# spartan6-2.net
KiCad netlist of a schematic drawn in Altium Designer
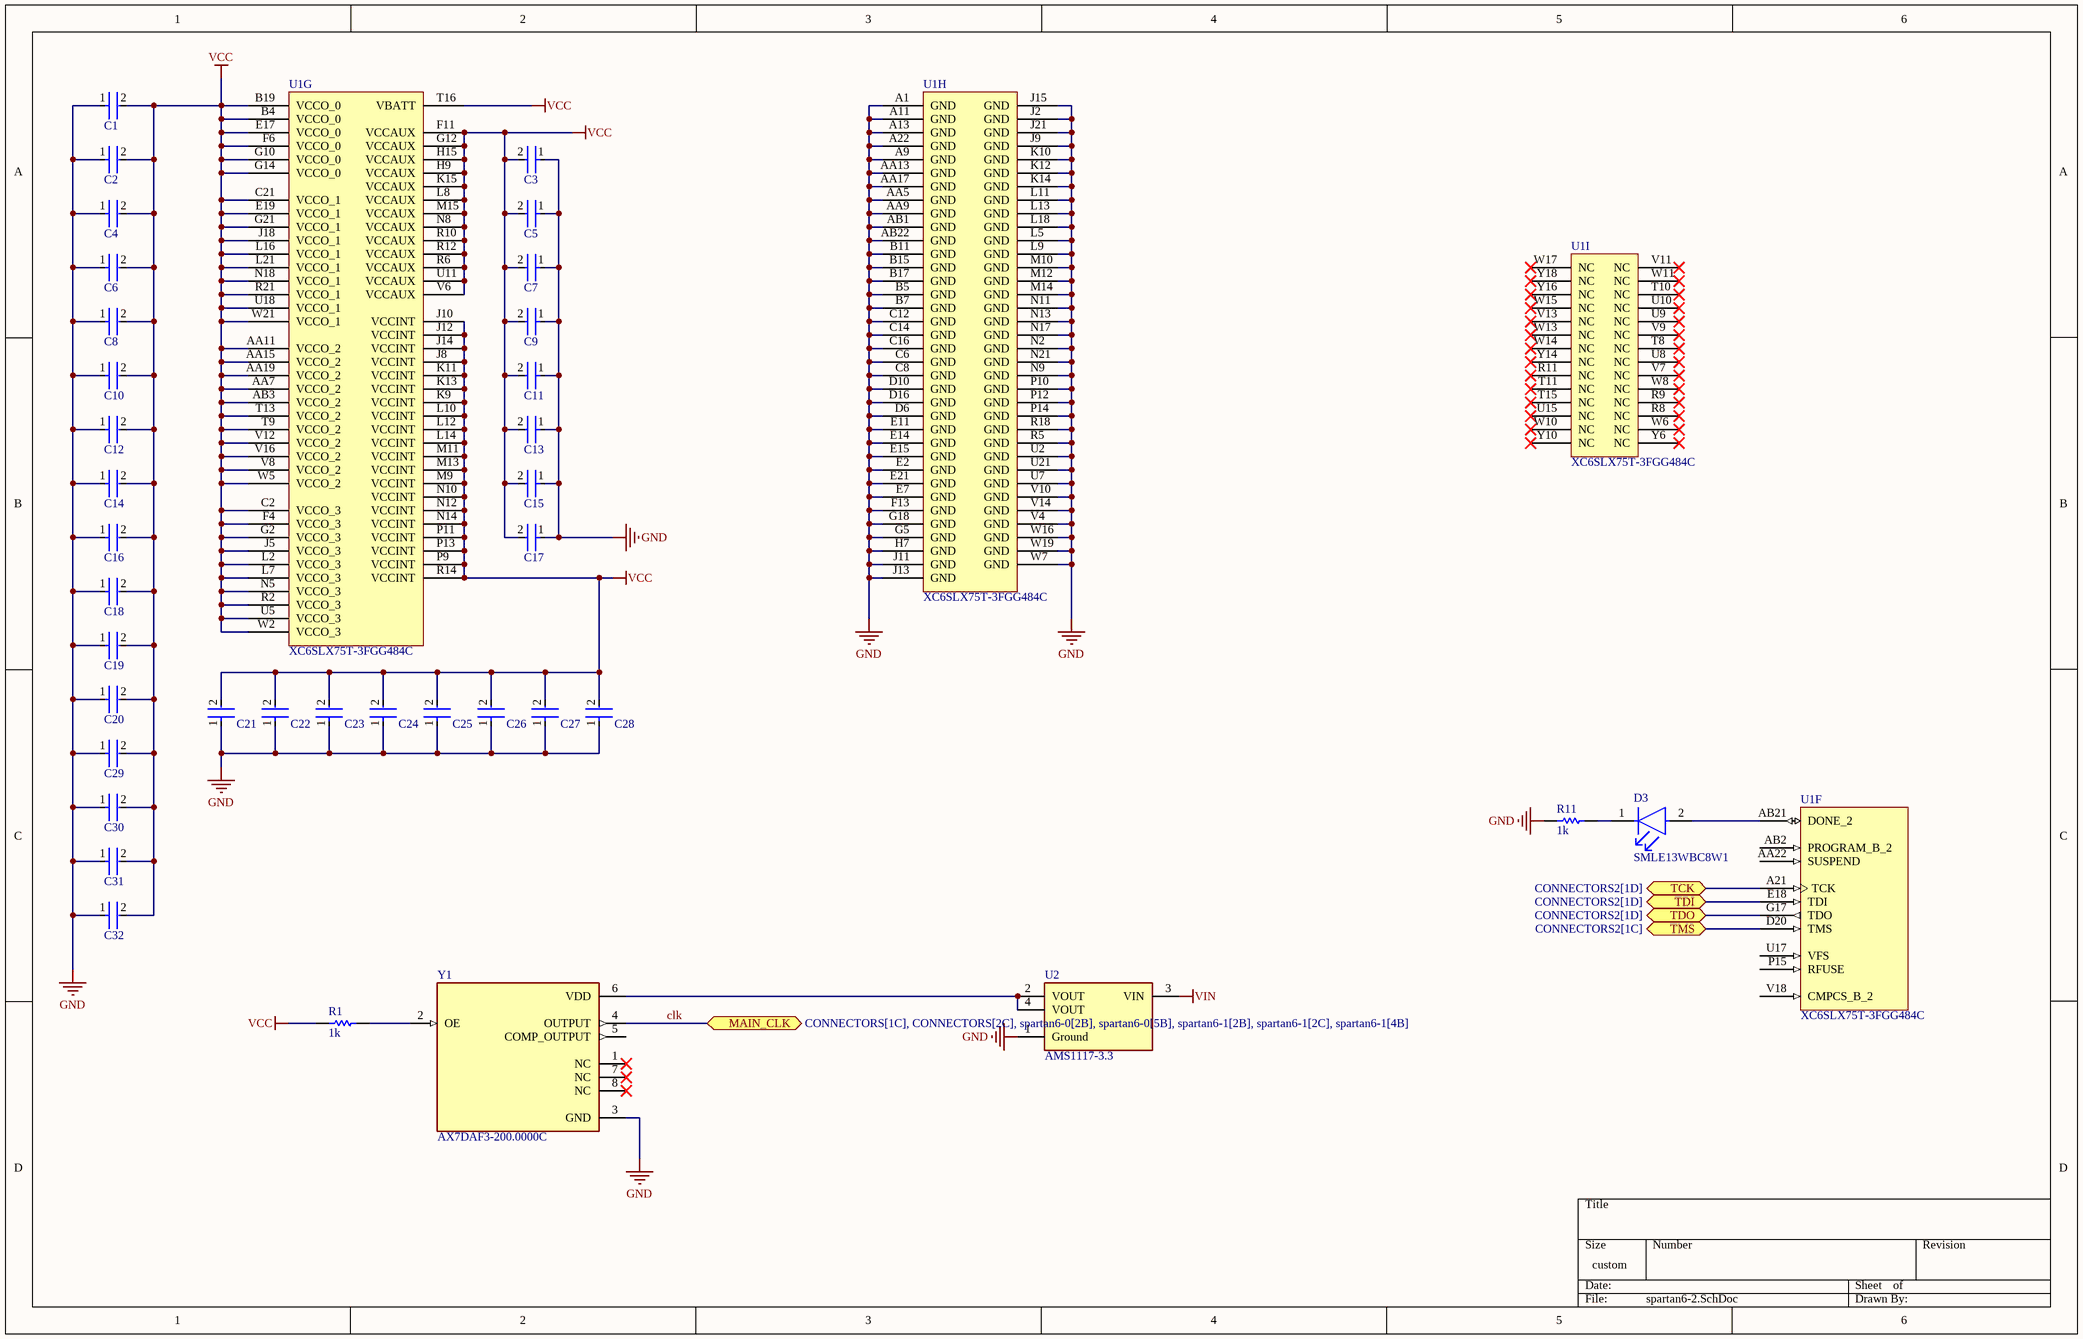
[diagram p0: spartan6-2.SchDoc]

(export (version "E")
  (design (tool "Eeschema 10.0.6"))
  (components
    (comp (ref "C1")
      (value "C0603X6S0G474M030BC")
      (footprint "FP-C0603-030-0_03-MFG")
      (description "Multilayer Ceramic Capacitors 470nF ±20% 4V X6S SMD 0201")
      (fields (field (name "TOLERANCE") "20%"))
      (libsource (lib "Altium Content Vault") (part "02cd4be3c70576c341d710602a673aa"))
    )
    (comp (ref "C2")
      (value "C0603X6S0G474M030BC")
      (footprint "FP-C0603-030-0_03-MFG")
      (description "Multilayer Ceramic Capacitors 470nF ±20% 4V X6S SMD 0201")
      (fields (field (name "TOLERANCE") "20%"))
      (libsource (lib "Altium Content Vault") (part "02cd4be3c70576c341d710602a673aa"))
    )
    (comp (ref "C3")
      (value "C0603X6S0G474M030BC")
      (footprint "FP-C0603-030-0_03-MFG")
      (description "Multilayer Ceramic Capacitors 470nF ±20% 4V X6S SMD 0201")
      (fields (field (name "TOLERANCE") "20%"))
      (libsource (lib "Altium Content Vault") (part "02cd4be3c70576c341d710602a673aa"))
    )
    (comp (ref "C4")
      (value "C0603X6S0G474M030BC")
      (footprint "FP-C0603-030-0_03-MFG")
      (description "Multilayer Ceramic Capacitors 470nF ±20% 4V X6S SMD 0201")
      (fields (field (name "TOLERANCE") "20%"))
      (libsource (lib "Altium Content Vault") (part "02cd4be3c70576c341d710602a673aa"))
    )
    (comp (ref "C5")
      (value "C0603X6S0G474M030BC")
      (footprint "FP-C0603-030-0_03-MFG")
      (description "Multilayer Ceramic Capacitors 470nF ±20% 4V X6S SMD 0201")
      (fields (field (name "TOLERANCE") "20%"))
      (libsource (lib "Altium Content Vault") (part "02cd4be3c70576c341d710602a673aa"))
    )
    (comp (ref "C6")
      (value "C0603X6S0G474M030BC")
      (footprint "FP-C0603-030-0_03-MFG")
      (description "Multilayer Ceramic Capacitors 470nF ±20% 4V X6S SMD 0201")
      (fields (field (name "TOLERANCE") "20%"))
      (libsource (lib "Altium Content Vault") (part "02cd4be3c70576c341d710602a673aa"))
    )
    (comp (ref "C7")
      (value "C0603X6S0G474M030BC")
      (footprint "FP-C0603-030-0_03-MFG")
      (description "Multilayer Ceramic Capacitors 470nF ±20% 4V X6S SMD 0201")
      (fields (field (name "TOLERANCE") "20%"))
      (libsource (lib "Altium Content Vault") (part "02cd4be3c70576c341d710602a673aa"))
    )
    (comp (ref "C8")
      (value "C0603X6S0G474M030BC")
      (footprint "FP-C0603-030-0_03-MFG")
      (description "Multilayer Ceramic Capacitors 470nF ±20% 4V X6S SMD 0201")
      (fields (field (name "TOLERANCE") "20%"))
      (libsource (lib "Altium Content Vault") (part "02cd4be3c70576c341d710602a673aa"))
    )
    (comp (ref "C9")
      (value "C0603X6S0G474M030BC")
      (footprint "FP-C0603-030-0_03-MFG")
      (description "Multilayer Ceramic Capacitors 470nF ±20% 4V X6S SMD 0201")
      (fields (field (name "TOLERANCE") "20%"))
      (libsource (lib "Altium Content Vault") (part "02cd4be3c70576c341d710602a673aa"))
    )
    (comp (ref "C10")
      (value "C0603X6S0G474M030BC")
      (footprint "FP-C0603-030-0_03-MFG")
      (description "Multilayer Ceramic Capacitors 470nF ±20% 4V X6S SMD 0201")
      (fields (field (name "TOLERANCE") "20%"))
      (libsource (lib "Altium Content Vault") (part "02cd4be3c70576c341d710602a673aa"))
    )
    (comp (ref "C11")
      (value "C0603X6S0G474M030BC")
      (footprint "FP-C0603-030-0_03-MFG")
      (description "Multilayer Ceramic Capacitors 470nF ±20% 4V X6S SMD 0201")
      (fields (field (name "TOLERANCE") "20%"))
      (libsource (lib "Altium Content Vault") (part "02cd4be3c70576c341d710602a673aa"))
    )
    (comp (ref "C12")
      (value "C0603X6S0G474M030BC")
      (footprint "FP-C0603-030-0_03-MFG")
      (description "Multilayer Ceramic Capacitors 470nF ±20% 4V X6S SMD 0201")
      (fields (field (name "TOLERANCE") "20%"))
      (libsource (lib "Altium Content Vault") (part "02cd4be3c70576c341d710602a673aa"))
    )
    (comp (ref "C13")
      (value "C0603X6S0G474M030BC")
      (footprint "FP-C0603-030-0_03-MFG")
      (description "Multilayer Ceramic Capacitors 470nF ±20% 4V X6S SMD 0201")
      (fields (field (name "TOLERANCE") "20%"))
      (libsource (lib "Altium Content Vault") (part "02cd4be3c70576c341d710602a673aa"))
    )
    (comp (ref "C14")
      (value "C0603X6S0G474M030BC")
      (footprint "FP-C0603-030-0_03-MFG")
      (description "Multilayer Ceramic Capacitors 470nF ±20% 4V X6S SMD 0201")
      (fields (field (name "TOLERANCE") "20%"))
      (libsource (lib "Altium Content Vault") (part "02cd4be3c70576c341d710602a673aa"))
    )
    (comp (ref "C15")
      (value "C0603X6S0G474M030BC")
      (footprint "FP-C0603-030-0_03-MFG")
      (description "Multilayer Ceramic Capacitors 470nF ±20% 4V X6S SMD 0201")
      (fields (field (name "TOLERANCE") "20%"))
      (libsource (lib "Altium Content Vault") (part "02cd4be3c70576c341d710602a673aa"))
    )
    (comp (ref "C16")
      (value "C0603X6S0G474M030BC")
      (footprint "FP-C0603-030-0_03-MFG")
      (description "Multilayer Ceramic Capacitors 470nF ±20% 4V X6S SMD 0201")
      (fields (field (name "TOLERANCE") "20%"))
      (libsource (lib "Altium Content Vault") (part "02cd4be3c70576c341d710602a673aa"))
    )
    (comp (ref "C17")
      (value "C0603X6S0G474M030BC")
      (footprint "FP-C0603-030-0_03-MFG")
      (description "Multilayer Ceramic Capacitors 470nF ±20% 4V X6S SMD 0201")
      (fields (field (name "TOLERANCE") "20%"))
      (libsource (lib "Altium Content Vault") (part "02cd4be3c70576c341d710602a673aa"))
    )
    (comp (ref "C18")
      (value "C0603X6S0G474M030BC")
      (footprint "FP-C0603-030-0_03-MFG")
      (description "Multilayer Ceramic Capacitors 470nF ±20% 4V X6S SMD 0201")
      (fields (field (name "TOLERANCE") "20%"))
      (libsource (lib "Altium Content Vault") (part "02cd4be3c70576c341d710602a673aa"))
    )
    (comp (ref "C19")
      (value "C0603X6S0G474M030BC")
      (footprint "FP-C0603-030-0_03-MFG")
      (description "Multilayer Ceramic Capacitors 470nF ±20% 4V X6S SMD 0201")
      (fields (field (name "TOLERANCE") "20%"))
      (libsource (lib "Altium Content Vault") (part "02cd4be3c70576c341d710602a673aa"))
    )
    (comp (ref "C20")
      (value "C0603X6S0G474M030BC")
      (footprint "FP-C0603-030-0_03-MFG")
      (description "Multilayer Ceramic Capacitors 470nF ±20% 4V X6S SMD 0201")
      (fields (field (name "TOLERANCE") "20%"))
      (libsource (lib "Altium Content Vault") (part "02cd4be3c70576c341d710602a673aa"))
    )
    (comp (ref "C21")
      (value "C0603X6S0G474M030BC")
      (footprint "FP-C0603-030-0_03-MFG")
      (description "Multilayer Ceramic Capacitors 470nF ±20% 4V X6S SMD 0201")
      (fields (field (name "TOLERANCE") "20%"))
      (libsource (lib "Altium Content Vault") (part "02cd4be3c70576c341d710602a673aa"))
    )
    (comp (ref "C22")
      (value "C0603X6S0G474M030BC")
      (footprint "FP-C0603-030-0_03-MFG")
      (description "Multilayer Ceramic Capacitors 470nF ±20% 4V X6S SMD 0201")
      (fields (field (name "TOLERANCE") "20%"))
      (libsource (lib "Altium Content Vault") (part "02cd4be3c70576c341d710602a673aa"))
    )
    (comp (ref "C23")
      (value "C0603X6S0G474M030BC")
      (footprint "FP-C0603-030-0_03-MFG")
      (description "Multilayer Ceramic Capacitors 470nF ±20% 4V X6S SMD 0201")
      (fields (field (name "TOLERANCE") "20%"))
      (libsource (lib "Altium Content Vault") (part "02cd4be3c70576c341d710602a673aa"))
    )
    (comp (ref "C24")
      (value "C0603X6S0G474M030BC")
      (footprint "FP-C0603-030-0_03-MFG")
      (description "Multilayer Ceramic Capacitors 470nF ±20% 4V X6S SMD 0201")
      (fields (field (name "TOLERANCE") "20%"))
      (libsource (lib "Altium Content Vault") (part "02cd4be3c70576c341d710602a673aa"))
    )
    (comp (ref "C25")
      (value "C0603X6S0G474M030BC")
      (footprint "FP-C0603-030-0_03-MFG")
      (description "Multilayer Ceramic Capacitors 470nF ±20% 4V X6S SMD 0201")
      (fields (field (name "TOLERANCE") "20%"))
      (libsource (lib "Altium Content Vault") (part "02cd4be3c70576c341d710602a673aa"))
    )
    (comp (ref "C26")
      (value "C0603X6S0G474M030BC")
      (footprint "FP-C0603-030-0_03-MFG")
      (description "Multilayer Ceramic Capacitors 470nF ±20% 4V X6S SMD 0201")
      (fields (field (name "TOLERANCE") "20%"))
      (libsource (lib "Altium Content Vault") (part "02cd4be3c70576c341d710602a673aa"))
    )
    (comp (ref "C27")
      (value "C0603X6S0G474M030BC")
      (footprint "FP-C0603-030-0_03-MFG")
      (description "Multilayer Ceramic Capacitors 470nF ±20% 4V X6S SMD 0201")
      (fields (field (name "TOLERANCE") "20%"))
      (libsource (lib "Altium Content Vault") (part "02cd4be3c70576c341d710602a673aa"))
    )
    (comp (ref "C28")
      (value "C0603X6S0G474M030BC")
      (footprint "FP-C0603-030-0_03-MFG")
      (description "Multilayer Ceramic Capacitors 470nF ±20% 4V X6S SMD 0201")
      (fields (field (name "TOLERANCE") "20%"))
      (libsource (lib "Altium Content Vault") (part "02cd4be3c70576c341d710602a673aa"))
    )
    (comp (ref "C29")
      (value "C0603X6S0G474M030BC")
      (footprint "FP-C0603-030-0_03-MFG")
      (description "Multilayer Ceramic Capacitors 470nF ±20% 4V X6S SMD 0201")
      (fields (field (name "TOLERANCE") "20%"))
      (libsource (lib "Altium Content Vault") (part "02cd4be3c70576c341d710602a673aa"))
    )
    (comp (ref "C30")
      (value "C0603X6S0G474M030BC")
      (footprint "FP-C0603-030-0_03-MFG")
      (description "Multilayer Ceramic Capacitors 470nF ±20% 4V X6S SMD 0201")
      (fields (field (name "TOLERANCE") "20%"))
      (libsource (lib "Altium Content Vault") (part "02cd4be3c70576c341d710602a673aa"))
    )
    (comp (ref "C31")
      (value "C0603X6S0G474M030BC")
      (footprint "FP-C0603-030-0_03-MFG")
      (description "Multilayer Ceramic Capacitors 470nF ±20% 4V X6S SMD 0201")
      (fields (field (name "TOLERANCE") "20%"))
      (libsource (lib "Altium Content Vault") (part "02cd4be3c70576c341d710602a673aa"))
    )
    (comp (ref "C32")
      (value "C0603X6S0G474M030BC")
      (footprint "FP-C0603-030-0_03-MFG")
      (description "Multilayer Ceramic Capacitors 470nF ±20% 4V X6S SMD 0201")
      (fields (field (name "TOLERANCE") "20%"))
      (libsource (lib "Altium Content Vault") (part "02cd4be3c70576c341d710602a673aa"))
    )
    (comp (ref "D3")
      (value "SMLE13WBC8W1")
      (footprint "FP-SMLE13WBC8W1-MFG")
      (description "LED WHITE 0603 SMD")
      (fields
        (field (name "OCTOPART") "https://octopart.com/smle13wbc8w1-rohm-22224565")
        (field (name "MANUFACTURER") "Rohm")
      )
      (libsource (lib "Altium Content Vault") (part "8706943c75ba83719d021d2fdc84c58"))
    )
    (comp (ref "R1")
      (value "1k")
      (footprint "RESC2013X60X35ML10T20")
      (fields (field (name "TOLERANCE") "5%") (field (name "MANUFACTURER") "Yageo"))
      (libsource (lib "Altium Content Vault") (part "RES-2"))
    )
    (comp (ref "R11")
      (value "1k")
      (footprint "RESC2013X60X35ML10T20")
      (fields (field (name "TOLERANCE") "5%") (field (name "MANUFACTURER") "Yageo"))
      (libsource (lib "Altium Content Vault") (part "RES-2"))
    )
    (comp (ref "U1")
      (value "XC6SLX75T-3FGG484C")
      (footprint "FGG484")
      (libsource (lib "Altium Content Vault") (part "FPGA-XSP6-XC6SLX75T-GA484"))
    )
    (comp (ref "U2")
      (value "AMS1117-3.3")
      (footprint "FP-AMS1117-IPC_C")
      (description "LDO Voltage Regulators 1A, 3.3V")
      (fields
        (field (name "OCTOPART") "https://octopart.com/ams1117-3.3-advanced+monolithic+systems-25899300")
        (field (name "MANUFACTURER") "Advanced Monolithic Systems")
      )
      (libsource (lib "Altium Content Vault") (part "8bdbb5f8e77002000e30dd2845d0354"))
    )
    (comp (ref "Y1")
      (value "AX7DAF3-200.0000C")
      (footprint "OSC_AX7DAF3-200.0000C")
      (fields (field (name "MF") "{'manufacturer': u'Abracon LLC'}"))
      (libsource (lib "AX7DAF3-200.0000C") (part "AX7DAF3-200.0000C"))
    )
  )
  (nets
    (net (code "1") (name "/TCK") (class "Default")
      (node (ref "U1") (pin "A21") (pinfunction "TCK_A21") (pintype "input"))
    )
    (net (code "2") (name "/TDI") (class "Default")
      (node (ref "U1") (pin "E18") (pinfunction "TDI_E18") (pintype "input"))
    )
    (net (code "3") (name "/TDO") (class "Default")
      (node (ref "U1") (pin "G17") (pinfunction "TDO_G17") (pintype "output"))
    )
    (net (code "4") (name "/TMS") (class "Default")
      (node (ref "U1") (pin "D20") (pinfunction "TMS_D20") (pintype "input"))
    )
    (net (code "5") (name "/clk") (class "Default")
      (node (ref "Y1") (pin "4") (pinfunction "OUTPUT_4") (pintype "output"))
    )
    (net (code "6") (name "GND") (class "Default")
      (node (ref "C1") (pin "1") (pinfunction "1_1") (pintype "passive"))
      (node (ref "C10") (pin "1") (pinfunction "1_1") (pintype "passive"))
      (node (ref "C11") (pin "1") (pinfunction "1_1") (pintype "passive"))
      (node (ref "C12") (pin "1") (pinfunction "1_1") (pintype "passive"))
      (node (ref "C13") (pin "1") (pinfunction "1_1") (pintype "passive"))
      (node (ref "C14") (pin "1") (pinfunction "1_1") (pintype "passive"))
      (node (ref "C15") (pin "1") (pinfunction "1_1") (pintype "passive"))
      (node (ref "C16") (pin "1") (pinfunction "1_1") (pintype "passive"))
      (node (ref "C17") (pin "1") (pinfunction "1_1") (pintype "passive"))
      (node (ref "C18") (pin "1") (pinfunction "1_1") (pintype "passive"))
      (node (ref "C19") (pin "1") (pinfunction "1_1") (pintype "passive"))
      (node (ref "C2") (pin "1") (pinfunction "1_1") (pintype "passive"))
      (node (ref "C20") (pin "1") (pinfunction "1_1") (pintype "passive"))
      (node (ref "C21") (pin "1") (pinfunction "1_1") (pintype "passive"))
      (node (ref "C22") (pin "1") (pinfunction "1_1") (pintype "passive"))
      (node (ref "C23") (pin "1") (pinfunction "1_1") (pintype "passive"))
      (node (ref "C24") (pin "1") (pinfunction "1_1") (pintype "passive"))
      (node (ref "C25") (pin "1") (pinfunction "1_1") (pintype "passive"))
      (node (ref "C26") (pin "1") (pinfunction "1_1") (pintype "passive"))
      (node (ref "C27") (pin "1") (pinfunction "1_1") (pintype "passive"))
      (node (ref "C28") (pin "1") (pinfunction "1_1") (pintype "passive"))
      (node (ref "C29") (pin "1") (pinfunction "1_1") (pintype "passive"))
      (node (ref "C3") (pin "1") (pinfunction "1_1") (pintype "passive"))
      (node (ref "C30") (pin "1") (pinfunction "1_1") (pintype "passive"))
      (node (ref "C31") (pin "1") (pinfunction "1_1") (pintype "passive"))
      (node (ref "C32") (pin "1") (pinfunction "1_1") (pintype "passive"))
      (node (ref "C4") (pin "1") (pinfunction "1_1") (pintype "passive"))
      (node (ref "C5") (pin "1") (pinfunction "1_1") (pintype "passive"))
      (node (ref "C6") (pin "1") (pinfunction "1_1") (pintype "passive"))
      (node (ref "C7") (pin "1") (pinfunction "1_1") (pintype "passive"))
      (node (ref "C8") (pin "1") (pinfunction "1_1") (pintype "passive"))
      (node (ref "C9") (pin "1") (pinfunction "1_1") (pintype "passive"))
      (node (ref "R11") (pin "1") (pinfunction "1_1") (pintype "passive"))
      (node (ref "U1") (pin "A1") (pinfunction "GND_A1") (pintype "power_in"))
      (node (ref "U1") (pin "A11") (pinfunction "GND_A11") (pintype "power_in"))
      (node (ref "U1") (pin "A13") (pinfunction "GND_A13") (pintype "power_in"))
      (node (ref "U1") (pin "A22") (pinfunction "GND_A22") (pintype "power_in"))
      (node (ref "U1") (pin "A9") (pinfunction "GND_A9") (pintype "power_in"))
      (node (ref "U1") (pin "AA13") (pinfunction "GND_AA13") (pintype "power_in"))
      (node (ref "U1") (pin "AA17") (pinfunction "GND_AA17") (pintype "power_in"))
      (node (ref "U1") (pin "AA5") (pinfunction "GND_AA5") (pintype "power_in"))
      (node (ref "U1") (pin "AA9") (pinfunction "GND_AA9") (pintype "power_in"))
      (node (ref "U1") (pin "AB1") (pinfunction "GND_AB1") (pintype "power_in"))
      (node (ref "U1") (pin "AB22") (pinfunction "GND_AB22") (pintype "power_in"))
      (node (ref "U1") (pin "B11") (pinfunction "GND_B11") (pintype "power_in"))
      (node (ref "U1") (pin "B15") (pinfunction "GND_B15") (pintype "power_in"))
      (node (ref "U1") (pin "B17") (pinfunction "GND_B17") (pintype "power_in"))
      (node (ref "U1") (pin "B5") (pinfunction "GND_B5") (pintype "power_in"))
      (node (ref "U1") (pin "B7") (pinfunction "GND_B7") (pintype "power_in"))
      (node (ref "U1") (pin "C12") (pinfunction "GND_C12") (pintype "power_in"))
      (node (ref "U1") (pin "C14") (pinfunction "GND_C14") (pintype "power_in"))
      (node (ref "U1") (pin "C16") (pinfunction "GND_C16") (pintype "power_in"))
      (node (ref "U1") (pin "C6") (pinfunction "GND_C6") (pintype "power_in"))
      (node (ref "U1") (pin "C8") (pinfunction "GND_C8") (pintype "power_in"))
      (node (ref "U1") (pin "D10") (pinfunction "GND_D10") (pintype "power_in"))
      (node (ref "U1") (pin "D16") (pinfunction "GND_D16") (pintype "power_in"))
      (node (ref "U1") (pin "D6") (pinfunction "GND_D6") (pintype "power_in"))
      (node (ref "U1") (pin "E11") (pinfunction "GND_E11") (pintype "power_in"))
      (node (ref "U1") (pin "E14") (pinfunction "GND_E14") (pintype "power_in"))
      (node (ref "U1") (pin "E15") (pinfunction "GND_E15") (pintype "power_in"))
      (node (ref "U1") (pin "E2") (pinfunction "GND_E2") (pintype "power_in"))
      (node (ref "U1") (pin "E21") (pinfunction "GND_E21") (pintype "power_in"))
      (node (ref "U1") (pin "E7") (pinfunction "GND_E7") (pintype "power_in"))
      (node (ref "U1") (pin "F13") (pinfunction "GND_F13") (pintype "power_in"))
      (node (ref "U1") (pin "G18") (pinfunction "GND_G18") (pintype "power_in"))
      (node (ref "U1") (pin "G5") (pinfunction "GND_G5") (pintype "power_in"))
      (node (ref "U1") (pin "H7") (pinfunction "GND_H7") (pintype "power_in"))
      (node (ref "U1") (pin "J11") (pinfunction "GND_J11") (pintype "power_in"))
      (node (ref "U1") (pin "J13") (pinfunction "GND_J13") (pintype "power_in"))
      (node (ref "U1") (pin "J15") (pinfunction "GND_J15") (pintype "power_in"))
      (node (ref "U1") (pin "J2") (pinfunction "GND_J2") (pintype "power_in"))
      (node (ref "U1") (pin "J21") (pinfunction "GND_J21") (pintype "power_in"))
      (node (ref "U1") (pin "J9") (pinfunction "GND_J9") (pintype "power_in"))
      (node (ref "U1") (pin "K10") (pinfunction "GND_K10") (pintype "power_in"))
      (node (ref "U1") (pin "K12") (pinfunction "GND_K12") (pintype "power_in"))
      (node (ref "U1") (pin "K14") (pinfunction "GND_K14") (pintype "power_in"))
      (node (ref "U1") (pin "L11") (pinfunction "GND_L11") (pintype "power_in"))
      (node (ref "U1") (pin "L13") (pinfunction "GND_L13") (pintype "power_in"))
      (node (ref "U1") (pin "L18") (pinfunction "GND_L18") (pintype "power_in"))
      (node (ref "U1") (pin "L5") (pinfunction "GND_L5") (pintype "power_in"))
      (node (ref "U1") (pin "L9") (pinfunction "GND_L9") (pintype "power_in"))
      (node (ref "U1") (pin "M10") (pinfunction "GND_M10") (pintype "power_in"))
      (node (ref "U1") (pin "M12") (pinfunction "GND_M12") (pintype "power_in"))
      (node (ref "U1") (pin "M14") (pinfunction "GND_M14") (pintype "power_in"))
      (node (ref "U1") (pin "N11") (pinfunction "GND_N11") (pintype "power_in"))
      (node (ref "U1") (pin "N13") (pinfunction "GND_N13") (pintype "power_in"))
      (node (ref "U1") (pin "N17") (pinfunction "GND_N17") (pintype "power_in"))
      (node (ref "U1") (pin "N2") (pinfunction "GND_N2") (pintype "power_in"))
      (node (ref "U1") (pin "N21") (pinfunction "GND_N21") (pintype "power_in"))
      (node (ref "U1") (pin "N9") (pinfunction "GND_N9") (pintype "power_in"))
      (node (ref "U1") (pin "P10") (pinfunction "GND_P10") (pintype "power_in"))
      (node (ref "U1") (pin "P12") (pinfunction "GND_P12") (pintype "power_in"))
      (node (ref "U1") (pin "P14") (pinfunction "GND_P14") (pintype "power_in"))
      (node (ref "U1") (pin "R18") (pinfunction "GND_R18") (pintype "power_in"))
      (node (ref "U1") (pin "R5") (pinfunction "GND_R5") (pintype "power_in"))
      (node (ref "U1") (pin "U2") (pinfunction "GND_U2") (pintype "power_in"))
      (node (ref "U1") (pin "U21") (pinfunction "GND_U21") (pintype "power_in"))
      (node (ref "U1") (pin "U7") (pinfunction "GND_U7") (pintype "power_in"))
      (node (ref "U1") (pin "V10") (pinfunction "GND_V10") (pintype "power_in"))
      (node (ref "U1") (pin "V14") (pinfunction "GND_V14") (pintype "power_in"))
      (node (ref "U1") (pin "V4") (pinfunction "GND_V4") (pintype "power_in"))
      (node (ref "U1") (pin "W16") (pinfunction "GND_W16") (pintype "power_in"))
      (node (ref "U1") (pin "W19") (pinfunction "GND_W19") (pintype "power_in"))
      (node (ref "U1") (pin "W7") (pinfunction "GND_W7") (pintype "power_in"))
      (node (ref "U2") (pin "1") (pinfunction "Ground_1") (pintype "power_in"))
      (node (ref "Y1") (pin "3") (pinfunction "GND_3") (pintype "power_in"))
    )
    (net (code "7") (name "Net-(D3-A)") (class "Default")
      (node (ref "D3") (pin "2") (pinfunction "A_2") (pintype "passive"))
      (node (ref "U1") (pin "AB21") (pinfunction "DONE_2_AB21") (pintype "bidirectional"))
    )
    (net (code "8") (name "Net-(D3-C)") (class "Default")
      (node (ref "D3") (pin "1") (pinfunction "C_1") (pintype "passive"))
      (node (ref "R11") (pin "2") (pinfunction "2_2") (pintype "passive"))
    )
    (net (code "9") (name "Net-(Y1-OE)") (class "Default")
      (node (ref "R1") (pin "2") (pinfunction "2_2") (pintype "passive"))
      (node (ref "Y1") (pin "2") (pinfunction "OE_2") (pintype "input"))
    )
    (net (code "10") (name "Net-(Y1-VDD)") (class "Default")
      (node (ref "U2") (pin "2") (pinfunction "VOUT_2") (pintype "passive"))
      (node (ref "U2") (pin "4") (pinfunction "VOUT_4") (pintype "passive"))
      (node (ref "Y1") (pin "6") (pinfunction "VDD_6") (pintype "power_in"))
    )
    (net (code "11") (name "VCC") (class "Default")
      (node (ref "C1") (pin "2") (pinfunction "2_2") (pintype "passive"))
      (node (ref "C10") (pin "2") (pinfunction "2_2") (pintype "passive"))
      (node (ref "C11") (pin "2") (pinfunction "2_2") (pintype "passive"))
      (node (ref "C12") (pin "2") (pinfunction "2_2") (pintype "passive"))
      (node (ref "C13") (pin "2") (pinfunction "2_2") (pintype "passive"))
      (node (ref "C14") (pin "2") (pinfunction "2_2") (pintype "passive"))
      (node (ref "C15") (pin "2") (pinfunction "2_2") (pintype "passive"))
      (node (ref "C16") (pin "2") (pinfunction "2_2") (pintype "passive"))
      (node (ref "C17") (pin "2") (pinfunction "2_2") (pintype "passive"))
      (node (ref "C18") (pin "2") (pinfunction "2_2") (pintype "passive"))
      (node (ref "C19") (pin "2") (pinfunction "2_2") (pintype "passive"))
      (node (ref "C2") (pin "2") (pinfunction "2_2") (pintype "passive"))
      (node (ref "C20") (pin "2") (pinfunction "2_2") (pintype "passive"))
      (node (ref "C21") (pin "2") (pinfunction "2_2") (pintype "passive"))
      (node (ref "C22") (pin "2") (pinfunction "2_2") (pintype "passive"))
      (node (ref "C23") (pin "2") (pinfunction "2_2") (pintype "passive"))
      (node (ref "C24") (pin "2") (pinfunction "2_2") (pintype "passive"))
      (node (ref "C25") (pin "2") (pinfunction "2_2") (pintype "passive"))
      (node (ref "C26") (pin "2") (pinfunction "2_2") (pintype "passive"))
      (node (ref "C27") (pin "2") (pinfunction "2_2") (pintype "passive"))
      (node (ref "C28") (pin "2") (pinfunction "2_2") (pintype "passive"))
      (node (ref "C29") (pin "2") (pinfunction "2_2") (pintype "passive"))
      (node (ref "C3") (pin "2") (pinfunction "2_2") (pintype "passive"))
      (node (ref "C30") (pin "2") (pinfunction "2_2") (pintype "passive"))
      (node (ref "C31") (pin "2") (pinfunction "2_2") (pintype "passive"))
      (node (ref "C32") (pin "2") (pinfunction "2_2") (pintype "passive"))
      (node (ref "C4") (pin "2") (pinfunction "2_2") (pintype "passive"))
      (node (ref "C5") (pin "2") (pinfunction "2_2") (pintype "passive"))
      (node (ref "C6") (pin "2") (pinfunction "2_2") (pintype "passive"))
      (node (ref "C7") (pin "2") (pinfunction "2_2") (pintype "passive"))
      (node (ref "C8") (pin "2") (pinfunction "2_2") (pintype "passive"))
      (node (ref "C9") (pin "2") (pinfunction "2_2") (pintype "passive"))
      (node (ref "R1") (pin "1") (pinfunction "1_1") (pintype "passive"))
      (node (ref "U1") (pin "AA11") (pinfunction "VCCO_2_AA11") (pintype "power_in"))
      (node (ref "U1") (pin "AA15") (pinfunction "VCCO_2_AA15") (pintype "power_in"))
      (node (ref "U1") (pin "AA19") (pinfunction "VCCO_2_AA19") (pintype "power_in"))
      (node (ref "U1") (pin "AA7") (pinfunction "VCCO_2_AA7") (pintype "power_in"))
      (node (ref "U1") (pin "AB3") (pinfunction "VCCO_2_AB3") (pintype "power_in"))
      (node (ref "U1") (pin "B19") (pinfunction "VCCO_0_B19") (pintype "power_in"))
      (node (ref "U1") (pin "B4") (pinfunction "VCCO_0_B4") (pintype "power_in"))
      (node (ref "U1") (pin "C2") (pinfunction "VCCO_3_C2") (pintype "power_in"))
      (node (ref "U1") (pin "C21") (pinfunction "VCCO_1_C21") (pintype "power_in"))
      (node (ref "U1") (pin "E17") (pinfunction "VCCO_0_E17") (pintype "power_in"))
      (node (ref "U1") (pin "E19") (pinfunction "VCCO_1_E19") (pintype "power_in"))
      (node (ref "U1") (pin "F11") (pinfunction "VCCAUX_F11") (pintype "power_in"))
      (node (ref "U1") (pin "F4") (pinfunction "VCCO_3_F4") (pintype "power_in"))
      (node (ref "U1") (pin "F6") (pinfunction "VCCO_0_F6") (pintype "power_in"))
      (node (ref "U1") (pin "G10") (pinfunction "VCCO_0_G10") (pintype "power_in"))
      (node (ref "U1") (pin "G12") (pinfunction "VCCAUX_G12") (pintype "power_in"))
      (node (ref "U1") (pin "G14") (pinfunction "VCCO_0_G14") (pintype "power_in"))
      (node (ref "U1") (pin "G2") (pinfunction "VCCO_3_G2") (pintype "power_in"))
      (node (ref "U1") (pin "G21") (pinfunction "VCCO_1_G21") (pintype "power_in"))
      (node (ref "U1") (pin "H15") (pinfunction "VCCAUX_H15") (pintype "power_in"))
      (node (ref "U1") (pin "H9") (pinfunction "VCCAUX_H9") (pintype "power_in"))
      (node (ref "U1") (pin "J10") (pinfunction "VCCINT_J10") (pintype "power_in"))
      (node (ref "U1") (pin "J12") (pinfunction "VCCINT_J12") (pintype "power_in"))
      (node (ref "U1") (pin "J14") (pinfunction "VCCINT_J14") (pintype "power_in"))
      (node (ref "U1") (pin "J18") (pinfunction "VCCO_1_J18") (pintype "power_in"))
      (node (ref "U1") (pin "J5") (pinfunction "VCCO_3_J5") (pintype "power_in"))
      (node (ref "U1") (pin "J8") (pinfunction "VCCINT_J8") (pintype "power_in"))
      (node (ref "U1") (pin "K11") (pinfunction "VCCINT_K11") (pintype "power_in"))
      (node (ref "U1") (pin "K13") (pinfunction "VCCINT_K13") (pintype "power_in"))
      (node (ref "U1") (pin "K15") (pinfunction "VCCAUX_K15") (pintype "power_in"))
      (node (ref "U1") (pin "K9") (pinfunction "VCCINT_K9") (pintype "power_in"))
      (node (ref "U1") (pin "L10") (pinfunction "VCCINT_L10") (pintype "power_in"))
      (node (ref "U1") (pin "L12") (pinfunction "VCCINT_L12") (pintype "power_in"))
      (node (ref "U1") (pin "L14") (pinfunction "VCCINT_L14") (pintype "power_in"))
      (node (ref "U1") (pin "L16") (pinfunction "VCCO_1_L16") (pintype "power_in"))
      (node (ref "U1") (pin "L2") (pinfunction "VCCO_3_L2") (pintype "power_in"))
      (node (ref "U1") (pin "L21") (pinfunction "VCCO_1_L21") (pintype "power_in"))
      (node (ref "U1") (pin "L7") (pinfunction "VCCO_3_L7") (pintype "power_in"))
      (node (ref "U1") (pin "L8") (pinfunction "VCCAUX_L8") (pintype "power_in"))
      (node (ref "U1") (pin "M11") (pinfunction "VCCINT_M11") (pintype "power_in"))
      (node (ref "U1") (pin "M13") (pinfunction "VCCINT_M13") (pintype "power_in"))
      (node (ref "U1") (pin "M15") (pinfunction "VCCAUX_M15") (pintype "power_in"))
      (node (ref "U1") (pin "M9") (pinfunction "VCCINT_M9") (pintype "power_in"))
      (node (ref "U1") (pin "N10") (pinfunction "VCCINT_N10") (pintype "power_in"))
      (node (ref "U1") (pin "N12") (pinfunction "VCCINT_N12") (pintype "power_in"))
      (node (ref "U1") (pin "N14") (pinfunction "VCCINT_N14") (pintype "power_in"))
      (node (ref "U1") (pin "N18") (pinfunction "VCCO_1_N18") (pintype "power_in"))
      (node (ref "U1") (pin "N5") (pinfunction "VCCO_3_N5") (pintype "power_in"))
      (node (ref "U1") (pin "N8") (pinfunction "VCCAUX_N8") (pintype "power_in"))
      (node (ref "U1") (pin "P11") (pinfunction "VCCINT_P11") (pintype "power_in"))
      (node (ref "U1") (pin "P13") (pinfunction "VCCINT_P13") (pintype "power_in"))
      (node (ref "U1") (pin "P9") (pinfunction "VCCINT_P9") (pintype "power_in"))
      (node (ref "U1") (pin "R10") (pinfunction "VCCAUX_R10") (pintype "power_in"))
      (node (ref "U1") (pin "R12") (pinfunction "VCCAUX_R12") (pintype "power_in"))
      (node (ref "U1") (pin "R14") (pinfunction "VCCINT_R14") (pintype "power_in"))
      (node (ref "U1") (pin "R2") (pinfunction "VCCO_3_R2") (pintype "power_in"))
      (node (ref "U1") (pin "R21") (pinfunction "VCCO_1_R21") (pintype "power_in"))
      (node (ref "U1") (pin "R6") (pinfunction "VCCAUX_R6") (pintype "power_in"))
      (node (ref "U1") (pin "T13") (pinfunction "VCCO_2_T13") (pintype "power_in"))
      (node (ref "U1") (pin "T16") (pinfunction "VBATT_T16") (pintype "power_in"))
      (node (ref "U1") (pin "T9") (pinfunction "VCCO_2_T9") (pintype "power_in"))
      (node (ref "U1") (pin "U11") (pinfunction "VCCAUX_U11") (pintype "power_in"))
      (node (ref "U1") (pin "U18") (pinfunction "VCCO_1_U18") (pintype "power_in"))
      (node (ref "U1") (pin "U5") (pinfunction "VCCO_3_U5") (pintype "power_in"))
      (node (ref "U1") (pin "V12") (pinfunction "VCCO_2_V12") (pintype "power_in"))
      (node (ref "U1") (pin "V16") (pinfunction "VCCO_2_V16") (pintype "power_in"))
      (node (ref "U1") (pin "V6") (pinfunction "VCCAUX_V6") (pintype "power_in"))
      (node (ref "U1") (pin "V8") (pinfunction "VCCO_2_V8") (pintype "power_in"))
      (node (ref "U1") (pin "W2") (pinfunction "VCCO_3_W2") (pintype "power_in"))
      (node (ref "U1") (pin "W21") (pinfunction "VCCO_1_W21") (pintype "power_in"))
      (node (ref "U1") (pin "W5") (pinfunction "VCCO_2_W5") (pintype "power_in"))
    )
    (net (code "12") (name "VIN") (class "Default")
      (node (ref "U2") (pin "3") (pinfunction "VIN_3") (pintype "power_in"))
    )
    (net (code "13") (name "unconnected-(U1F-CMPCS_B_2-PadV18)") (class "Default")
      (node (ref "U1") (pin "V18") (pinfunction "CMPCS_B_2_V18") (pintype "input"))
    )
    (net (code "14") (name "unconnected-(U1F-PROGRAM_B_2-PadAB2)") (class "Default")
      (node (ref "U1") (pin "AB2") (pinfunction "PROGRAM_B_2_AB2") (pintype "input"))
    )
    (net (code "15") (name "unconnected-(U1F-RFUSE-PadP15)") (class "Default")
      (node (ref "U1") (pin "P15") (pinfunction "RFUSE_P15") (pintype "input"))
    )
    (net (code "16") (name "unconnected-(U1F-SUSPEND-PadAA22)") (class "Default")
      (node (ref "U1") (pin "AA22") (pinfunction "SUSPEND_AA22") (pintype "input"))
    )
    (net (code "17") (name "unconnected-(U1F-VFS-PadU17)") (class "Default")
      (node (ref "U1") (pin "U17") (pinfunction "VFS_U17") (pintype "input"))
    )
    (net (code "18") (name "unconnected-(U1I-NC-PadR8)") (class "Default")
      (node (ref "U1") (pin "R8") (pinfunction "NC_R8") (pintype "passive+no_connect"))
    )
    (net (code "19") (name "unconnected-(U1I-NC-PadR9)") (class "Default")
      (node (ref "U1") (pin "R9") (pinfunction "NC_R9") (pintype "passive+no_connect"))
    )
    (net (code "20") (name "unconnected-(U1I-NC-PadR11)") (class "Default")
      (node (ref "U1") (pin "R11") (pinfunction "NC_R11") (pintype "passive+no_connect"))
    )
    (net (code "21") (name "unconnected-(U1I-NC-PadT8)") (class "Default")
      (node (ref "U1") (pin "T8") (pinfunction "NC_T8") (pintype "passive+no_connect"))
    )
    (net (code "22") (name "unconnected-(U1I-NC-PadT10)") (class "Default")
      (node (ref "U1") (pin "T10") (pinfunction "NC_T10") (pintype "passive+no_connect"))
    )
    (net (code "23") (name "unconnected-(U1I-NC-PadT11)") (class "Default")
      (node (ref "U1") (pin "T11") (pinfunction "NC_T11") (pintype "passive+no_connect"))
    )
    (net (code "24") (name "unconnected-(U1I-NC-PadT15)") (class "Default")
      (node (ref "U1") (pin "T15") (pinfunction "NC_T15") (pintype "passive+no_connect"))
    )
    (net (code "25") (name "unconnected-(U1I-NC-PadU8)") (class "Default")
      (node (ref "U1") (pin "U8") (pinfunction "NC_U8") (pintype "passive+no_connect"))
    )
    (net (code "26") (name "unconnected-(U1I-NC-PadU9)") (class "Default")
      (node (ref "U1") (pin "U9") (pinfunction "NC_U9") (pintype "passive+no_connect"))
    )
    (net (code "27") (name "unconnected-(U1I-NC-PadU10)") (class "Default")
      (node (ref "U1") (pin "U10") (pinfunction "NC_U10") (pintype "passive+no_connect"))
    )
    (net (code "28") (name "unconnected-(U1I-NC-PadU15)") (class "Default")
      (node (ref "U1") (pin "U15") (pinfunction "NC_U15") (pintype "passive+no_connect"))
    )
    (net (code "29") (name "unconnected-(U1I-NC-PadV7)") (class "Default")
      (node (ref "U1") (pin "V7") (pinfunction "NC_V7") (pintype "passive+no_connect"))
    )
    (net (code "30") (name "unconnected-(U1I-NC-PadV9)") (class "Default")
      (node (ref "U1") (pin "V9") (pinfunction "NC_V9") (pintype "passive+no_connect"))
    )
    (net (code "31") (name "unconnected-(U1I-NC-PadV11)") (class "Default")
      (node (ref "U1") (pin "V11") (pinfunction "NC_V11") (pintype "passive+no_connect"))
    )
    (net (code "32") (name "unconnected-(U1I-NC-PadV13)") (class "Default")
      (node (ref "U1") (pin "V13") (pinfunction "NC_V13") (pintype "passive+no_connect"))
    )
    (net (code "33") (name "unconnected-(U1I-NC-PadW6)") (class "Default")
      (node (ref "U1") (pin "W6") (pinfunction "NC_W6") (pintype "passive+no_connect"))
    )
    (net (code "34") (name "unconnected-(U1I-NC-PadW8)") (class "Default")
      (node (ref "U1") (pin "W8") (pinfunction "NC_W8") (pintype "passive+no_connect"))
    )
    (net (code "35") (name "unconnected-(U1I-NC-PadW10)") (class "Default")
      (node (ref "U1") (pin "W10") (pinfunction "NC_W10") (pintype "passive+no_connect"))
    )
    (net (code "36") (name "unconnected-(U1I-NC-PadW11)") (class "Default")
      (node (ref "U1") (pin "W11") (pinfunction "NC_W11") (pintype "passive+no_connect"))
    )
    (net (code "37") (name "unconnected-(U1I-NC-PadW13)") (class "Default")
      (node (ref "U1") (pin "W13") (pinfunction "NC_W13") (pintype "passive+no_connect"))
    )
    (net (code "38") (name "unconnected-(U1I-NC-PadW14)") (class "Default")
      (node (ref "U1") (pin "W14") (pinfunction "NC_W14") (pintype "passive+no_connect"))
    )
    (net (code "39") (name "unconnected-(U1I-NC-PadW15)") (class "Default")
      (node (ref "U1") (pin "W15") (pinfunction "NC_W15") (pintype "passive+no_connect"))
    )
    (net (code "40") (name "unconnected-(U1I-NC-PadW17)") (class "Default")
      (node (ref "U1") (pin "W17") (pinfunction "NC_W17") (pintype "passive+no_connect"))
    )
    (net (code "41") (name "unconnected-(U1I-NC-PadY6)") (class "Default")
      (node (ref "U1") (pin "Y6") (pinfunction "NC_Y6") (pintype "passive+no_connect"))
    )
    (net (code "42") (name "unconnected-(U1I-NC-PadY10)") (class "Default")
      (node (ref "U1") (pin "Y10") (pinfunction "NC_Y10") (pintype "passive+no_connect"))
    )
    (net (code "43") (name "unconnected-(U1I-NC-PadY14)") (class "Default")
      (node (ref "U1") (pin "Y14") (pinfunction "NC_Y14") (pintype "passive+no_connect"))
    )
    (net (code "44") (name "unconnected-(U1I-NC-PadY16)") (class "Default")
      (node (ref "U1") (pin "Y16") (pinfunction "NC_Y16") (pintype "passive+no_connect"))
    )
    (net (code "45") (name "unconnected-(U1I-NC-PadY18)") (class "Default")
      (node (ref "U1") (pin "Y18") (pinfunction "NC_Y18") (pintype "passive+no_connect"))
    )
    (net (code "46") (name "unconnected-(Y1-COMP_OUTPUT-Pad5)") (class "Default")
      (node (ref "Y1") (pin "5") (pinfunction "COMP_OUTPUT_5") (pintype "output"))
    )
    (net (code "47") (name "unconnected-(Y1-NC-Pad1)") (class "Default")
      (node (ref "Y1") (pin "1") (pinfunction "NC_1") (pintype "passive+no_connect"))
    )
    (net (code "48") (name "unconnected-(Y1-NC-Pad7)") (class "Default")
      (node (ref "Y1") (pin "7") (pinfunction "NC_7") (pintype "passive+no_connect"))
    )
    (net (code "49") (name "unconnected-(Y1-NC-Pad8)") (class "Default")
      (node (ref "Y1") (pin "8") (pinfunction "NC_8") (pintype "passive+no_connect"))
    )
  )
)
